# SparkFun-74HC4051-8-Channel-Mux-Breakout.net
KiCad netlist of a schematic drawn in EAGLE
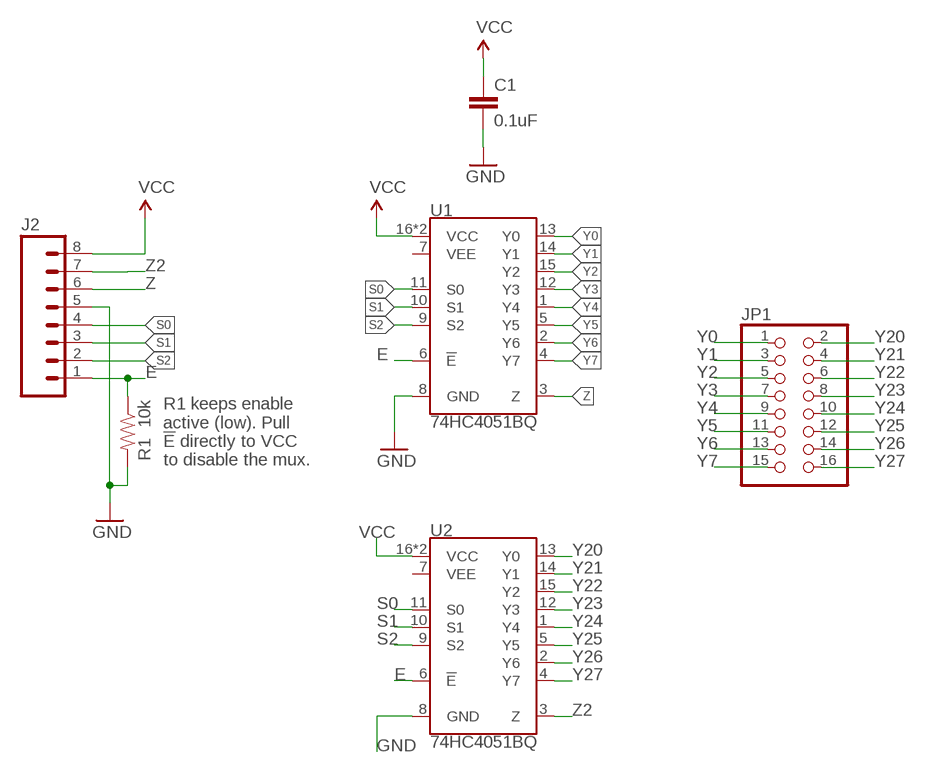
[diagram p0: schematic, sheet 1]

(export (version "E")
  (design (tool "Eeschema 10.0.6"))
  (components
    (comp (ref "C1")
      (value "0.1uF")
      (footprint "eagle-import:0603")
      (libsource (lib "eagle-import") (part "0.1UF-0603-25V-(+80/-20%)"))
    )
    (comp (ref "J2")
      (value "M08")
      (footprint "eagle-import:1X08_ROUND")
      (libsource (lib "eagle-import") (part "M08"))
    )
    (comp (ref "JP1")
      (value "PINHD-2X8")
      (footprint "eagle-import:2X08")
      (libsource (lib "eagle-import") (part "PINHD-2X8"))
    )
    (comp (ref "R1")
      (value "10k")
      (footprint "eagle-import:0603")
      (libsource (lib "eagle-import") (part "10KOHM-0603-1/10W-1%"))
    )
    (comp (ref "U1")
      (value "74HC4051BQ")
      (footprint "eagle-import:DHVQFN-16-2.5X3.5MM")
      (libsource (lib "eagle-import") (part "74HC4051BQ"))
    )
    (comp (ref "U2")
      (value "74HC4051BQ")
      (footprint "eagle-import:DHVQFN-16-2.5X3.5MM")
      (libsource (lib "eagle-import") (part "74HC4051BQ"))
    )
  )
  (nets
    (net (code "1") (name "/E") (class "Default")
      (node (ref "J2") (pin "1") (pinfunction "1_1") (pintype "passive"))
      (node (ref "R1") (pin "1") (pinfunction "1_1") (pintype "passive"))
      (node (ref "U1") (pin "6") (pinfunction "~{E}_6") (pintype "bidirectional"))
      (node (ref "U2") (pin "6") (pinfunction "~{E}_6") (pintype "bidirectional"))
    )
    (net (code "2") (name "/Y20") (class "Default")
      (node (ref "JP1") (pin "2") (pinfunction "2_2") (pintype "passive"))
      (node (ref "U2") (pin "13") (pinfunction "Y0_13") (pintype "bidirectional"))
    )
    (net (code "3") (name "/Y21") (class "Default")
      (node (ref "JP1") (pin "4") (pinfunction "4_4") (pintype "passive"))
      (node (ref "U2") (pin "14") (pinfunction "Y1_14") (pintype "bidirectional"))
    )
    (net (code "4") (name "/Y22") (class "Default")
      (node (ref "JP1") (pin "6") (pinfunction "6_6") (pintype "passive"))
      (node (ref "U2") (pin "15") (pinfunction "Y2_15") (pintype "bidirectional"))
    )
    (net (code "5") (name "/Y23") (class "Default")
      (node (ref "JP1") (pin "8") (pinfunction "8_8") (pintype "passive"))
      (node (ref "U2") (pin "12") (pinfunction "Y3_12") (pintype "bidirectional"))
    )
    (net (code "6") (name "/Y24") (class "Default")
      (node (ref "JP1") (pin "10") (pinfunction "10_10") (pintype "passive"))
      (node (ref "U2") (pin "1") (pinfunction "Y4_1") (pintype "bidirectional"))
    )
    (net (code "7") (name "/Y25") (class "Default")
      (node (ref "JP1") (pin "12") (pinfunction "12_12") (pintype "passive"))
      (node (ref "U2") (pin "5") (pinfunction "Y5_5") (pintype "bidirectional"))
    )
    (net (code "8") (name "/Y26") (class "Default")
      (node (ref "JP1") (pin "14") (pinfunction "14_14") (pintype "passive"))
      (node (ref "U2") (pin "2") (pinfunction "Y6_2") (pintype "bidirectional"))
    )
    (net (code "9") (name "/Y27") (class "Default")
      (node (ref "JP1") (pin "16") (pinfunction "16_16") (pintype "passive"))
      (node (ref "U2") (pin "4") (pinfunction "Y7_4") (pintype "bidirectional"))
    )
    (net (code "10") (name "/Z2") (class "Default")
      (node (ref "J2") (pin "7") (pinfunction "7_7") (pintype "passive"))
      (node (ref "U2") (pin "3") (pinfunction "Z_3") (pintype "bidirectional"))
    )
    (net (code "11") (name "GND") (class "Default")
      (node (ref "C1") (pin "2") (pinfunction "2_2") (pintype "passive"))
      (node (ref "J2") (pin "5") (pinfunction "5_5") (pintype "passive"))
      (node (ref "R1") (pin "2") (pinfunction "2_2") (pintype "passive"))
      (node (ref "U1") (pin "8") (pinfunction "GND_8") (pintype "bidirectional"))
      (node (ref "U2") (pin "8") (pinfunction "GND_8") (pintype "bidirectional"))
    )
    (net (code "12") (name "S0") (class "Default")
      (node (ref "J2") (pin "4") (pinfunction "4_4") (pintype "passive"))
      (node (ref "U1") (pin "11") (pinfunction "S0_11") (pintype "bidirectional"))
      (node (ref "U2") (pin "11") (pinfunction "S0_11") (pintype "bidirectional"))
    )
    (net (code "13") (name "S1") (class "Default")
      (node (ref "J2") (pin "3") (pinfunction "3_3") (pintype "passive"))
      (node (ref "U1") (pin "10") (pinfunction "S1_10") (pintype "bidirectional"))
      (node (ref "U2") (pin "10") (pinfunction "S1_10") (pintype "bidirectional"))
    )
    (net (code "14") (name "S2") (class "Default")
      (node (ref "J2") (pin "2") (pinfunction "2_2") (pintype "passive"))
      (node (ref "U1") (pin "9") (pinfunction "S2_9") (pintype "bidirectional"))
      (node (ref "U2") (pin "9") (pinfunction "S2_9") (pintype "bidirectional"))
    )
    (net (code "15") (name "VCC") (class "Default")
      (node (ref "C1") (pin "1") (pinfunction "1_1") (pintype "passive"))
      (node (ref "J2") (pin "8") (pinfunction "8_8") (pintype "passive"))
      (node (ref "U1") (pin "16") (pinfunction "VCC_16") (pintype "bidirectional"))
      (node (ref "U1") (pin "EP") (pinfunction "VCC_EP") (pintype "bidirectional"))
      (node (ref "U2") (pin "16") (pinfunction "VCC_16") (pintype "bidirectional"))
      (node (ref "U2") (pin "EP") (pinfunction "VCC_EP") (pintype "bidirectional"))
    )
    (net (code "16") (name "Y0") (class "Default")
      (node (ref "JP1") (pin "1") (pinfunction "1_1") (pintype "passive"))
      (node (ref "U1") (pin "13") (pinfunction "Y0_13") (pintype "bidirectional"))
    )
    (net (code "17") (name "Y1") (class "Default")
      (node (ref "JP1") (pin "3") (pinfunction "3_3") (pintype "passive"))
      (node (ref "U1") (pin "14") (pinfunction "Y1_14") (pintype "bidirectional"))
    )
    (net (code "18") (name "Y2") (class "Default")
      (node (ref "JP1") (pin "5") (pinfunction "5_5") (pintype "passive"))
      (node (ref "U1") (pin "15") (pinfunction "Y2_15") (pintype "bidirectional"))
    )
    (net (code "19") (name "Y3") (class "Default")
      (node (ref "JP1") (pin "7") (pinfunction "7_7") (pintype "passive"))
      (node (ref "U1") (pin "12") (pinfunction "Y3_12") (pintype "bidirectional"))
    )
    (net (code "20") (name "Y4") (class "Default")
      (node (ref "JP1") (pin "9") (pinfunction "9_9") (pintype "passive"))
      (node (ref "U1") (pin "1") (pinfunction "Y4_1") (pintype "bidirectional"))
    )
    (net (code "21") (name "Y5") (class "Default")
      (node (ref "JP1") (pin "11") (pinfunction "11_11") (pintype "passive"))
      (node (ref "U1") (pin "5") (pinfunction "Y5_5") (pintype "bidirectional"))
    )
    (net (code "22") (name "Y6") (class "Default")
      (node (ref "JP1") (pin "13") (pinfunction "13_13") (pintype "passive"))
      (node (ref "U1") (pin "2") (pinfunction "Y6_2") (pintype "bidirectional"))
    )
    (net (code "23") (name "Y7") (class "Default")
      (node (ref "JP1") (pin "15") (pinfunction "15_15") (pintype "passive"))
      (node (ref "U1") (pin "4") (pinfunction "Y7_4") (pintype "bidirectional"))
    )
    (net (code "24") (name "Z") (class "Default")
      (node (ref "J2") (pin "6") (pinfunction "6_6") (pintype "passive"))
      (node (ref "U1") (pin "3") (pinfunction "Z_3") (pintype "bidirectional"))
    )
    (net (code "25") (name "unconnected-(U1-VEE-Pad7)") (class "Default")
      (node (ref "U1") (pin "7") (pinfunction "VEE_7") (pintype "bidirectional"))
    )
    (net (code "26") (name "unconnected-(U2-VEE-Pad7)") (class "Default")
      (node (ref "U2") (pin "7") (pinfunction "VEE_7") (pintype "bidirectional"))
    )
  )
)
